# POWER.net
KiCad netlist of a schematic drawn in Altium Designer
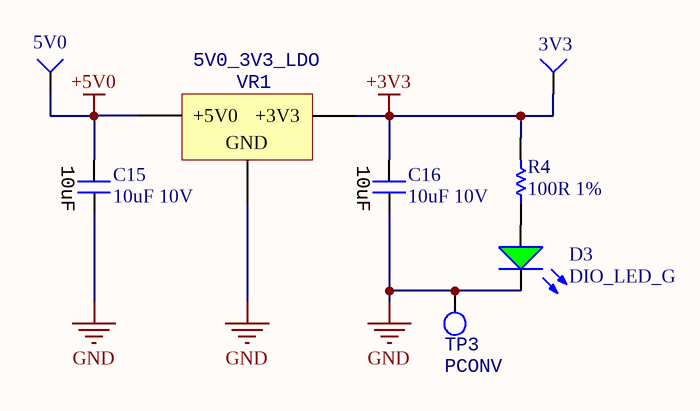
[diagram p0: POWER.SchDoc]

(export (version "E")
  (design (tool "Eeschema 10.0.6"))
  (components
    (comp (ref "C15")
      (value "10uF 10V")
      (footprint "CAPC0603(1608)55_N")
      (description "CAP CER 10UF 10V X5R 0603")
      (fields (field (name "MPN") "CC0603MRX5R6BB106") (field (name "MANUFACTURER") "Yageo"))
      (libsource (lib "UWRT_Schematic_Library_2020") (part "CAP_10uF_0603"))
    )
    (comp (ref "C16")
      (value "10uF 10V")
      (footprint "CAPC0603(1608)55_N")
      (description "CAP CER 10UF 10V X5R 0603")
      (fields (field (name "MPN") "CC0603MRX5R6BB106") (field (name "MANUFACTURER") "Yageo"))
      (libsource (lib "UWRT_Schematic_Library_2020") (part "CAP_10uF_0603"))
    )
    (comp (ref "D3")
      (value "DIO_LED_G")
      (footprint "LED_0805_LINE")
      (description "LED GREEN DIFFUSED 0805 SMD")
      (fields (field (name "MPN") "LG R971-KN-1") (field (name "MANUFACTURER") "OSRAM"))
      (libsource (lib "UWRT_Schematic_Library_2020") (part "DIO_LED_G"))
    )
    (comp (ref "R4")
      (value "100R 1%")
      (footprint "RESC0603(1608)_N")
      (description "RES SMD 100 OHM 1% 1/10W 0603")
      (fields (field (name "MANUFACTURER") "Yageo") (field (name "MPN") "RC0603FR-07100RL"))
      (libsource (lib "UWRT_Schematic_Library_2020") (part "RES_100R_0603"))
    )
    (comp (ref "TP1")
      (value "5V0")
      (footprint "TESTPOINT")
      (description "TESTPOINT_SMD")
      (libsource (lib "UWRT_Schematic_Library_2020") (part "*"))
    )
    (comp (ref "TP3")
      (value "PCONV")
      (footprint "TESTPOINT_LOOP")
      (description "Loop testpoint through-hole pad")
      (libsource (lib "UWRT_Schematic_Library_2020") (part "TESTPOINT_LOOP"))
    )
    (comp (ref "T_3V3")
      (value "3V3")
      (footprint "TESTPOINT")
      (description "TESTPOINT_SMD")
      (libsource (lib "UWRT_Schematic_Library_2020") (part "*"))
    )
    (comp (ref "VR1")
      (value "5V0_3V3_LDO")
      (footprint "UWRT_Footprint_Library_2019:VOLTAGE_REGULATOR")
      (description "IC REG LINEAR 3.3V 1A DPAK")
      (fields (field (name "PART NUMBER") "NCP1117DT33T5G") (field (name "MANUFACTURER") "ON Semiconductor"))
      (libsource (lib "UWRT_Schematic_Library_2019") (part "5V0_3V3_LDO"))
    )
  )
  (nets
    (net (code "1") (name "+3V3") (class "Default")
      (node (ref "C16") (pin "1") (pinfunction "1_1") (pintype "passive"))
      (node (ref "R4") (pin "2") (pinfunction "2_2") (pintype "passive"))
      (node (ref "T_3V3") (pin "1") (pinfunction "=value_1") (pintype "passive"))
      (node (ref "VR1") (pin "3") (pinfunction "+3V3_3") (pintype "passive"))
    )
    (net (code "2") (name "+5V0") (class "Default")
      (node (ref "C15") (pin "1") (pinfunction "1_1") (pintype "passive"))
      (node (ref "TP1") (pin "1") (pinfunction "=value_1") (pintype "passive"))
      (node (ref "VR1") (pin "1") (pinfunction "+5V0_1") (pintype "passive"))
    )
    (net (code "3") (name "GND") (class "Default")
      (node (ref "C15") (pin "2") (pinfunction "2_2") (pintype "passive"))
      (node (ref "C16") (pin "2") (pinfunction "2_2") (pintype "passive"))
      (node (ref "D3") (pin "2") (pinfunction "K_2") (pintype "passive"))
      (node (ref "TP3") (pin "1") (pintype "passive"))
      (node (ref "VR1") (pin "2") (pinfunction "GND_2") (pintype "passive"))
    )
    (net (code "4") (name "Net-(D3-A)") (class "Default")
      (node (ref "D3") (pin "1") (pinfunction "A_1") (pintype "passive"))
      (node (ref "R4") (pin "1") (pinfunction "1_1") (pintype "passive"))
    )
  )
)
